# 3.net
KiCad netlist of a schematic drawn in Altium Designer
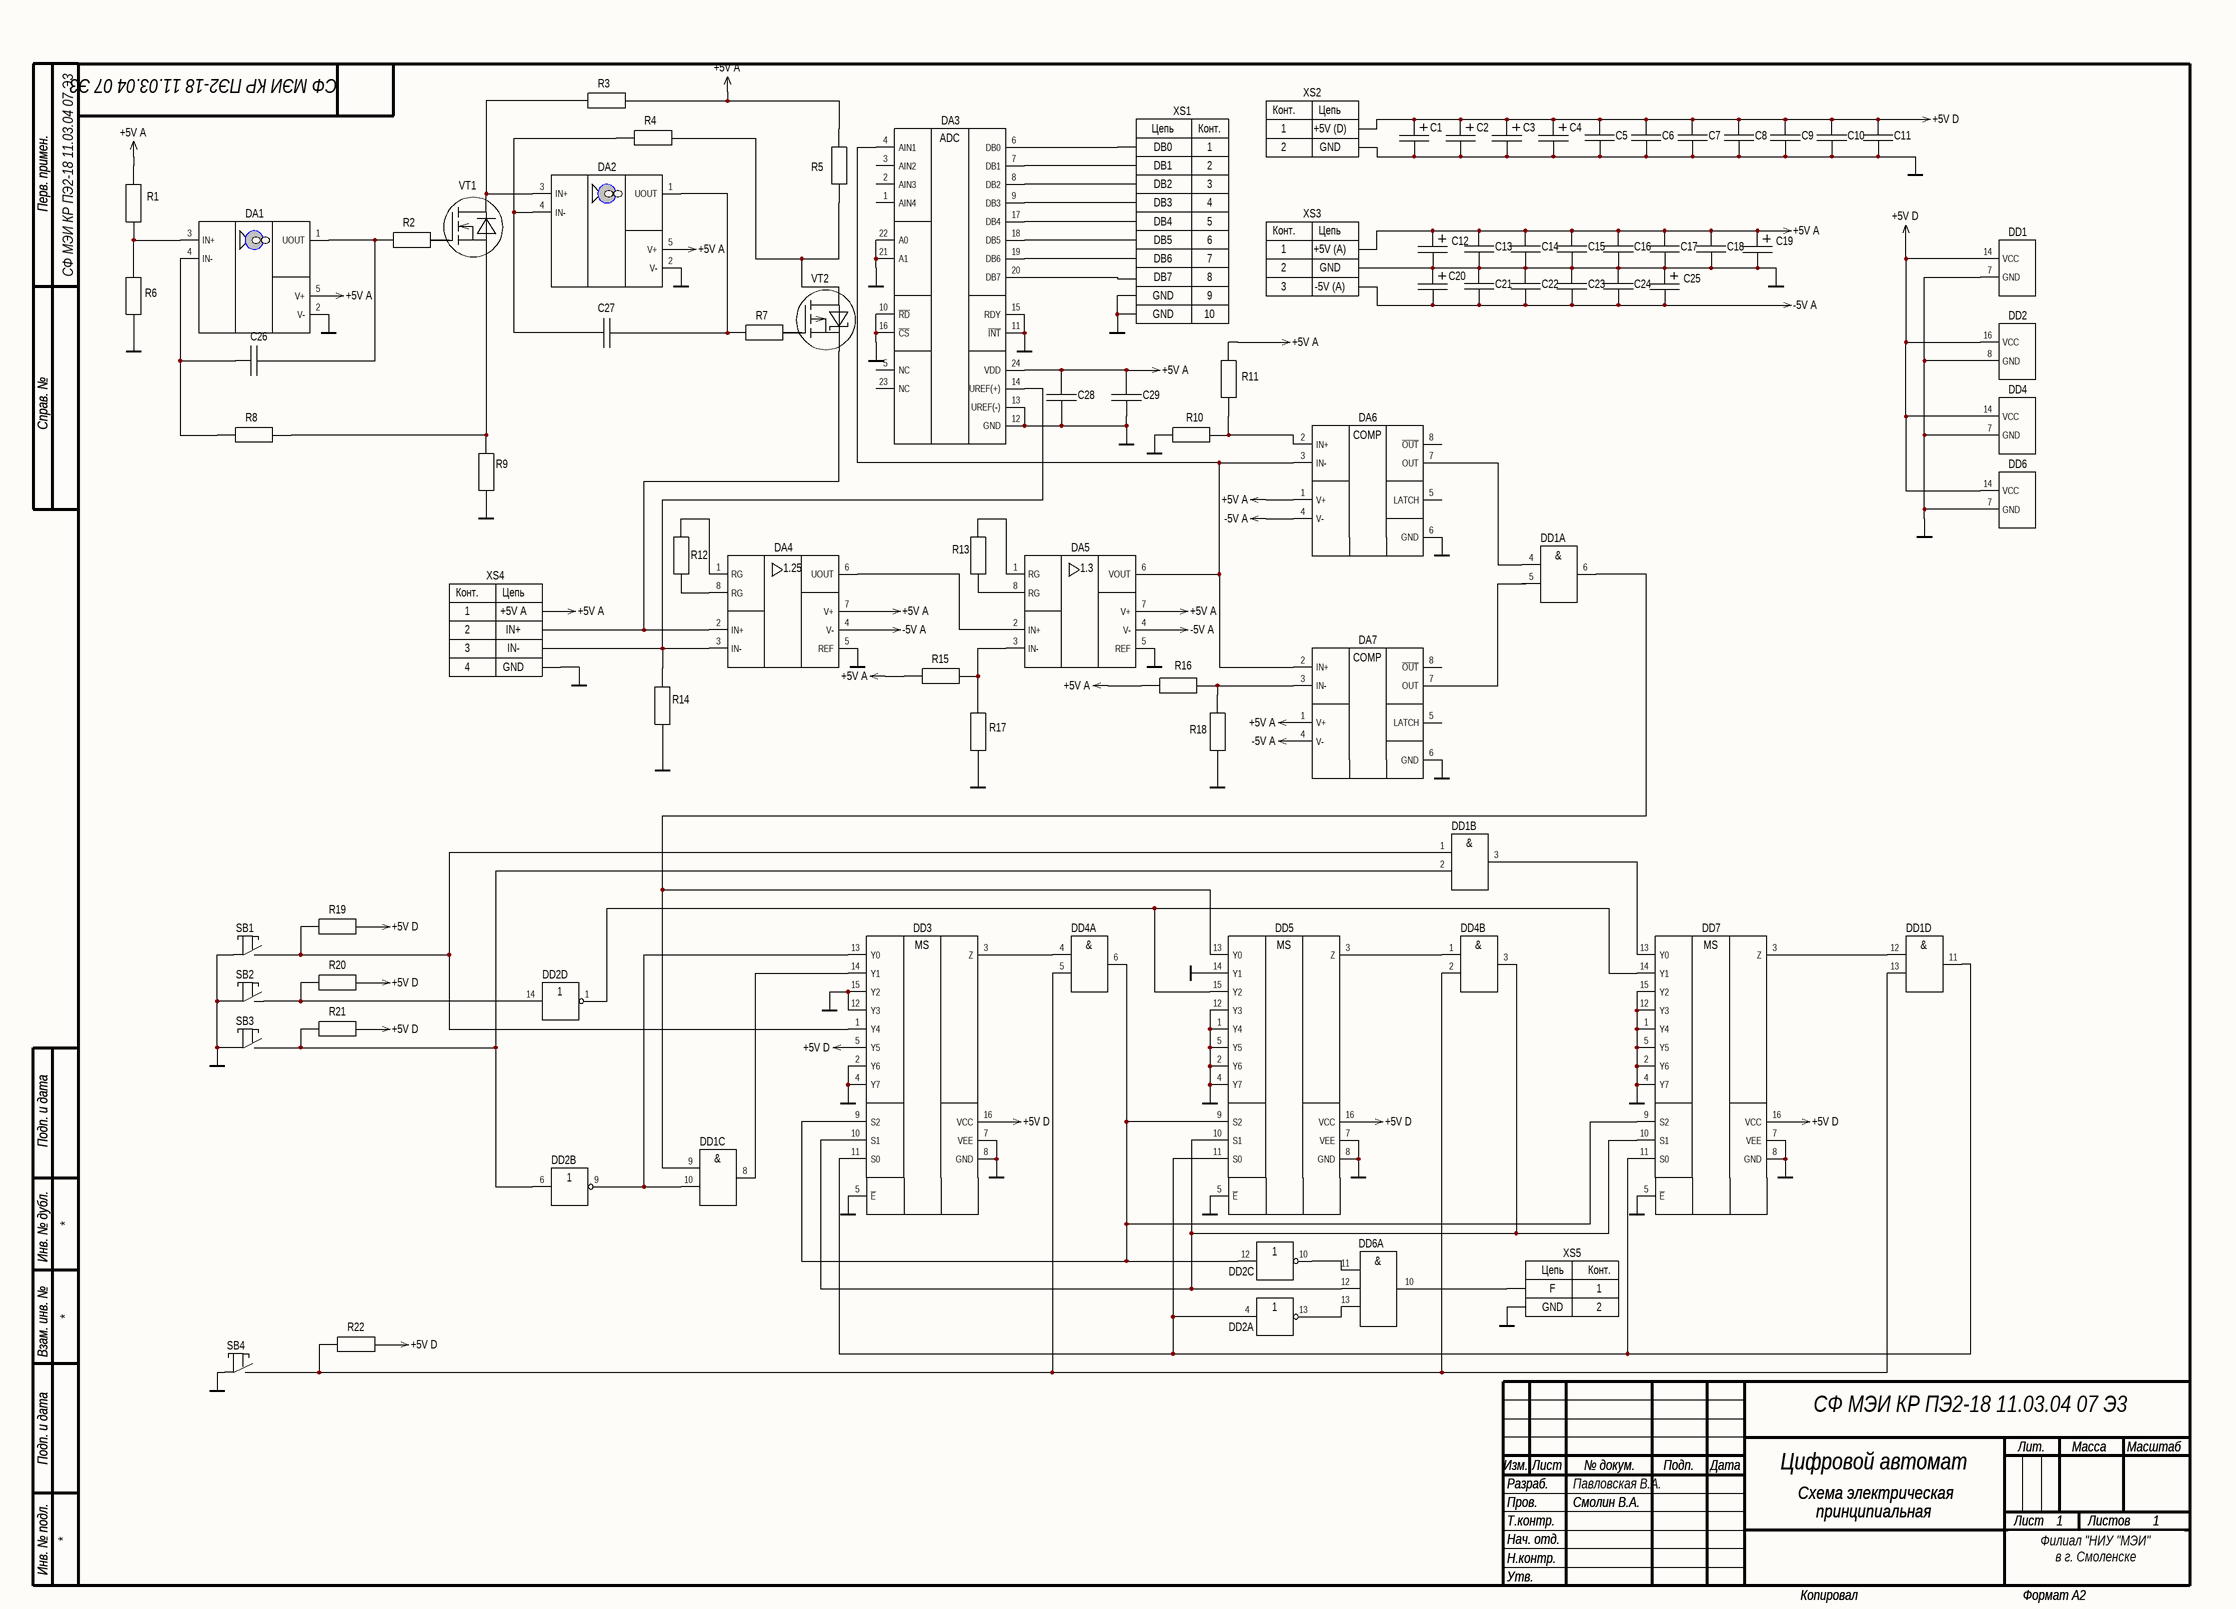
[diagram p0: Схема принципиальная3.SchDoc]

(export (version "E")
  (design (tool "Eeschema 10.0.6"))
  (components
    (comp (ref "C5")
      (value "0.1uF")
      (footprint "Кер.ЧИП конд. 0.1 мкФ X7R 50В 10% 0805")
      (description "Кер.ЧИП конд. 0.1 мкФ X7R 50В 10% 0805")
      (libsource (lib "УГО") (part "Кер.ЧИП конд. 0.1 мкФ X7R 50В 10% 0805"))
    )
    (comp (ref "C6")
      (value "0.1uF")
      (footprint "Кер.ЧИП конд. 0.1 мкФ X7R 50В 10% 0805")
      (description "Кер.ЧИП конд. 0.1 мкФ X7R 50В 10% 0805")
      (libsource (lib "УГО") (part "Кер.ЧИП конд. 0.1 мкФ X7R 50В 10% 0805"))
    )
    (comp (ref "C7")
      (value "0.1uF")
      (footprint "Кер.ЧИП конд. 0.1 мкФ X7R 50В 10% 0805")
      (description "Кер.ЧИП конд. 0.1 мкФ X7R 50В 10% 0805")
      (libsource (lib "УГО") (part "Кер.ЧИП конд. 0.1 мкФ X7R 50В 10% 0805"))
    )
    (comp (ref "C8")
      (value "0.1uF")
      (footprint "Кер.ЧИП конд. 0.1 мкФ X7R 50В 10% 0805")
      (description "Кер.ЧИП конд. 0.1 мкФ X7R 50В 10% 0805")
      (libsource (lib "УГО") (part "Кер.ЧИП конд. 0.1 мкФ X7R 50В 10% 0805"))
    )
    (comp (ref "C9")
      (value "0.1uF")
      (footprint "Кер.ЧИП конд. 0.1 мкФ X7R 50В 10% 0805")
      (description "Кер.ЧИП конд. 0.1 мкФ X7R 50В 10% 0805")
      (libsource (lib "УГО") (part "Кер.ЧИП конд. 0.1 мкФ X7R 50В 10% 0805"))
    )
    (comp (ref "C10")
      (value "0.1uF")
      (footprint "Кер.ЧИП конд. 0.1 мкФ X7R 50В 10% 0805")
      (description "Кер.ЧИП конд. 0.1 мкФ X7R 50В 10% 0805")
      (libsource (lib "УГО") (part "Кер.ЧИП конд. 0.1 мкФ X7R 50В 10% 0805"))
    )
    (comp (ref "C11")
      (value "0.1uF")
      (footprint "Кер.ЧИП конд. 0.1 мкФ X7R 50В 10% 0805")
      (description "Кер.ЧИП конд. 0.1 мкФ X7R 50В 10% 0805")
      (libsource (lib "УГО") (part "Кер.ЧИП конд. 0.1 мкФ X7R 50В 10% 0805"))
    )
    (comp (ref "C13")
      (value "0.1uF")
      (footprint "Кер.ЧИП конд. 0.1 мкФ X7R 50В 10% 0805")
      (description "Кер.ЧИП конд. 0.1 мкФ X7R 50В 10% 0805")
      (libsource (lib "УГО") (part "Кер.ЧИП конд. 0.1 мкФ X7R 50В 10% 0805"))
    )
    (comp (ref "C14")
      (value "0.1uF")
      (footprint "Кер.ЧИП конд. 0.1 мкФ X7R 50В 10% 0805")
      (description "Кер.ЧИП конд. 0.1 мкФ X7R 50В 10% 0805")
      (libsource (lib "УГО") (part "Кер.ЧИП конд. 0.1 мкФ X7R 50В 10% 0805"))
    )
    (comp (ref "C15")
      (value "0.1uF")
      (footprint "Кер.ЧИП конд. 0.1 мкФ X7R 50В 10% 0805")
      (description "Кер.ЧИП конд. 0.1 мкФ X7R 50В 10% 0805")
      (libsource (lib "УГО") (part "Кер.ЧИП конд. 0.1 мкФ X7R 50В 10% 0805"))
    )
    (comp (ref "C16")
      (value "0.1uF")
      (footprint "Кер.ЧИП конд. 0.1 мкФ X7R 50В 10% 0805")
      (description "Кер.ЧИП конд. 0.1 мкФ X7R 50В 10% 0805")
      (libsource (lib "УГО") (part "Кер.ЧИП конд. 0.1 мкФ X7R 50В 10% 0805"))
    )
    (comp (ref "C17")
      (value "0.1uF")
      (footprint "Кер.ЧИП конд. 0.1 мкФ X7R 50В 10% 0805")
      (description "Кер.ЧИП конд. 0.1 мкФ X7R 50В 10% 0805")
      (libsource (lib "УГО") (part "Кер.ЧИП конд. 0.1 мкФ X7R 50В 10% 0805"))
    )
    (comp (ref "C18")
      (value "0.1uF")
      (footprint "Кер.ЧИП конд. 0.1 мкФ X7R 50В 10% 0805")
      (description "Кер.ЧИП конд. 0.1 мкФ X7R 50В 10% 0805")
      (libsource (lib "УГО") (part "Кер.ЧИП конд. 0.1 мкФ X7R 50В 10% 0805"))
    )
    (comp (ref "C21")
      (value "0.1uF")
      (footprint "Кер.ЧИП конд. 0.1 мкФ X7R 50В 10% 0805")
      (description "Кер.ЧИП конд. 0.1 мкФ X7R 50В 10% 0805")
      (libsource (lib "УГО") (part "Кер.ЧИП конд. 0.1 мкФ X7R 50В 10% 0805"))
    )
    (comp (ref "C22")
      (value "0.1uF")
      (footprint "Кер.ЧИП конд. 0.1 мкФ X7R 50В 10% 0805")
      (description "Кер.ЧИП конд. 0.1 мкФ X7R 50В 10% 0805")
      (libsource (lib "УГО") (part "Кер.ЧИП конд. 0.1 мкФ X7R 50В 10% 0805"))
    )
    (comp (ref "C23")
      (value "0.1uF")
      (footprint "Кер.ЧИП конд. 0.1 мкФ X7R 50В 10% 0805")
      (description "Кер.ЧИП конд. 0.1 мкФ X7R 50В 10% 0805")
      (libsource (lib "УГО") (part "Кер.ЧИП конд. 0.1 мкФ X7R 50В 10% 0805"))
    )
    (comp (ref "C24")
      (value "0.1uF")
      (footprint "Кер.ЧИП конд. 0.1 мкФ X7R 50В 10% 0805")
      (description "Кер.ЧИП конд. 0.1 мкФ X7R 50В 10% 0805")
      (libsource (lib "УГО") (part "Кер.ЧИП конд. 0.1 мкФ X7R 50В 10% 0805"))
    )
    (comp (ref "C26")
      (value "1000pF")
      (footprint "Кер.ЧИП конд. 100пФ NPO 50В 5% 0805, GRM2165C1H101J")
      (description "Кер.ЧИП конд. 100пФ NPO 50В 5% 0805, GRM2165C1H101J")
      (libsource (lib "УГО") (part "Кер.ЧИП конд. 100пФ NPO 50В 5% 0805, GRM2165C1H101J"))
    )
    (comp (ref "C27")
      (value "2200pF")
      (footprint "Кер.ЧИП конд. 100пФ NPO 50В 5% 0805, GRM2165C1H101J")
      (description "Кер.ЧИП конд. 100пФ NPO 50В 5% 0805, GRM2165C1H101J")
      (libsource (lib "УГО") (part "Кер.ЧИП конд. 100пФ NPO 50В 5% 0805, GRM2165C1H101J"))
    )
    (comp (ref "C28")
      (value "0.1uF")
      (footprint "Кер.ЧИП конд. 0.1 мкФ X7R 50В 10% 0805")
      (description "Кер.ЧИП конд. 0.1 мкФ X7R 50В 10% 0805")
      (libsource (lib "УГО") (part "Кер.ЧИП конд. 0.1 мкФ X7R 50В 10% 0805"))
    )
    (comp (ref "C29")
      (value "47uF")
      (footprint "Кер.ЧИП конд. 47 мкФ X5R 20% 10В 1206")
      (description "Кер.ЧИП конд. 47 мкФ X5R 20% 10В 1206")
      (libsource (lib "УГО") (part "Кер.ЧИП конд. 47 мкФ X5R 20% 10В 1206"))
    )
    (comp (ref "DA1")
      (value "DA6")
      (footprint "ОУ для источника тока")
      (description "ОУ")
      (libsource (lib "УГО") (part "OPAx333 1.8-V, microPower, CMOS Operational Amplifiers, Zero-Drift Series"))
    )
    (comp (ref "DA2")
      (value "DA7")
      (footprint "ОУ для источника тока")
      (description "ОУ")
      (libsource (lib "УГО") (part "OPAx333 1.8-V, microPower, CMOS Operational Amplifiers, Zero-Drift Series"))
    )
    (comp (ref "DA4")
      (value "INA118E_BB")
      (footprint "AD620 Инструмент.усилитель")
      (libsource (lib "УГО") (part "INA118E_BB"))
    )
    (comp (ref "DA5")
      (value "INA118E_BB_1")
      (footprint "AD620 Инструмент.усилитель")
      (libsource (lib "УГО") (part "INA118E_BB_1"))
    )
    (comp (ref "DA6") (value "AD8561") (footprint "AD8561") (libsource (lib "УГО") (part "AD8561")))
    (comp (ref "DA7") (value "AD8561") (footprint "AD8561") (libsource (lib "УГО") (part "AD8561")))
    (comp (ref "DA33") (value "AD7824") (footprint "AD7824") (libsource (lib "УГО") (part "AD7824")))
    (comp (ref "DD1")
      (value "И №1 (4 компонента)")
      (footprint "4x2И")
      (libsource (lib "УГО") (part "И №1 (4 компонента)"))
    )
    (comp (ref "DD2")
      (value "НЕ №3 (4 компонента)")
      (footprint "CD4044B")
      (libsource (lib "УГО") (part "НЕ №3 (4 компонента)"))
    )
    (comp (ref "DD3")
      (value "74HC40510")
      (footprint "Мультиплексор")
      (libsource (lib "УГО") (part "Мультиплексор"))
    )
    (comp (ref "DD4")
      (value "И №2 (2 компонента)")
      (footprint "4x2И")
      (libsource (lib "УГО") (part "И №2 (2 компонента)"))
    )
    (comp (ref "DD5")
      (value "74HC40510")
      (footprint "Мультиплексор")
      (libsource (lib "УГО") (part "Мультиплексор"))
    )
    (comp (ref "DD6") (value "3И №1") (footprint "4x2И") (libsource (lib "УГО") (part "3И №1")))
    (comp (ref "DD7")
      (value "74HC40510")
      (footprint "Мультиплексор")
      (libsource (lib "УГО") (part "Мультиплексор"))
    )
    (comp (ref "R1")
      (value "3k")
      (footprint "0.125Вт 0805 3 кОм, 5%, Чип резистор (SMD)")
      (description "0.125Вт 0805 5кОм, 5%, Чип резистор (SMD)")
      (libsource (lib "УГО") (part "0.125Вт 0805 5кОм, 5%, Чип резистор (SMD)"))
    )
    (comp (ref "R2")
      (value "200")
      (footprint "0.125Вт 0805 3 кОм, 5%, Чип резистор (SMD)")
      (description "0.125Вт 0805 5кОм, 5%, Чип резистор (SMD)")
      (libsource (lib "УГО") (part "0.125Вт 0805 5кОм, 5%, Чип резистор (SMD)"))
    )
    (comp (ref "R3")
      (value "470")
      (footprint "0.125Вт 0805 3 кОм, 5%, Чип резистор (SMD)")
      (description "0.125Вт 0805 5кОм, 5%, Чип резистор (SMD)")
      (libsource (lib "УГО") (part "0.125Вт 0805 5кОм, 5%, Чип резистор (SMD)"))
    )
    (comp (ref "R4")
      (value "10k")
      (footprint "0.125Вт 0805 3 кОм, 5%, Чип резистор (SMD)")
      (description "0.125Вт 0805 5кОм, 5%, Чип резистор (SMD)")
      (libsource (lib "УГО") (part "0.125Вт 0805 5кОм, 5%, Чип резистор (SMD)"))
    )
    (comp (ref "R5")
      (value "4.7")
      (footprint "0.125Вт 0805 3 кОм, 5%, Чип резистор (SMD)")
      (description "0.125Вт 0805 5кОм, 5%, Чип резистор (SMD)")
      (libsource (lib "УГО") (part "0.125Вт 0805 5кОм, 5%, Чип резистор (SMD)"))
    )
    (comp (ref "R6")
      (value "2k")
      (footprint "0.125Вт 0805 3 кОм, 5%, Чип резистор (SMD)")
      (description "0.125Вт 0805 5кОм, 5%, Чип резистор (SMD)")
      (libsource (lib "УГО") (part "0.125Вт 0805 5кОм, 5%, Чип резистор (SMD)"))
    )
    (comp (ref "R7")
      (value "330")
      (footprint "0.125Вт 0805 3 кОм, 5%, Чип резистор (SMD)")
      (description "0.125Вт 0805 5кОм, 5%, Чип резистор (SMD)")
      (libsource (lib "УГО") (part "0.125Вт 0805 5кОм, 5%, Чип резистор (SMD)"))
    )
    (comp (ref "R8")
      (value "10k")
      (footprint "0.125Вт 0805 3 кОм, 5%, Чип резистор (SMD)")
      (description "0.125Вт 0805 5кОм, 5%, Чип резистор (SMD)")
      (libsource (lib "УГО") (part "0.125Вт 0805 5кОм, 5%, Чип резистор (SMD)"))
    )
    (comp (ref "R9")
      (value "2k")
      (footprint "0.125Вт 0805 3 кОм, 5%, Чип резистор (SMD)")
      (description "0.125Вт 0805 5кОм, 5%, Чип резистор (SMD)")
      (libsource (lib "УГО") (part "0.125Вт 0805 5кОм, 5%, Чип резистор (SMD)"))
    )
    (comp (ref "R10")
      (value "1.5k")
      (footprint "0.125Вт 0805 15Ом, 5%, Чип резистор (SMD)")
      (description "0.125Вт 0805 15Ом, 5%, Чип резистор (SMD)")
      (libsource (lib "УГО") (part "0.125Вт 0805 15Ом, 5%, Чип резистор (SMD)_2_1"))
    )
    (comp (ref "R11")
      (value "8.2k")
      (footprint "0.125Вт 0805 82Ом, 5%, Чип резистор (SMD)")
      (description "0.125Вт 0805 82Ом, 5%, Чип резистор (SMD)")
      (libsource (lib "УГО") (part "0.125Вт 0805 82Ом, 5%, Чип резистор (SMD)_2_2"))
    )
    (comp (ref "R12")
      (value "200k")
      (footprint "0.125Вт 0805 200 кОм, 5%, Чип резистор (SMD)")
      (description "0.125Вт 0805 200 кОм, 5%, Чип резистор (SMD)")
      (libsource (lib "УГО") (part "0.125Вт 0805 200 кОм, 5%, Чип резистор (SMD)"))
    )
    (comp (ref "R13")
      (value "160k")
      (footprint "0.125Вт 0805 160 кОм, 5%, Чип резистор (SMD)")
      (description "0.125Вт 0805 160 кОм, 5%, Чип резистор (SMD)")
      (libsource (lib "УГО") (part "0.125Вт 0805 160 кОм, 5%, Чип резистор (SMD)"))
    )
    (comp (ref "R14")
      (value "51k")
      (footprint "0.125Вт 0805 51 кОм, 5%, Чип резистор (SMD)")
      (description "0.125Вт 0805 51 кОм, 5%, Чип резистор (SMD)")
      (libsource (lib "УГО") (part "0.125Вт 0805 51 кОм, 5%, Чип резистор (SMD)"))
    )
    (comp (ref "R15")
      (value "7.5k")
      (footprint "0.125Вт 0805 75Ом, 5%, Чип резистор (SMD)")
      (description "0.125Вт 0805 75Ом, 5%, Чип резистор (SMD)")
      (libsource (lib "УГО") (part "0.125Вт 0805 75Ом, 5%, Чип резистор (SMD)"))
    )
    (comp (ref "R16")
      (value "1k")
      (footprint "0.125Вт 0805 91Ом, 5%, Чип резистор (SMD)")
      (description "0.125Вт 0805 91Ом, 5%, Чип резистор (SMD)")
      (libsource (lib "УГО") (part "0.125Вт 0805 91кОм, 5%, Чип резистор (SMD)_1"))
    )
    (comp (ref "R17")
      (value "2.2k")
      (footprint "0.125Вт 0805 22Ом, 5%, Чип резистор (SMD)")
      (description "0.125Вт 0805 22Ом, 5%, Чип резистор (SMD)")
      (libsource (lib "УГО") (part "0.125Вт 0805 22Ом, 5%, Чип резистор (SMD)"))
    )
    (comp (ref "R18")
      (value "56")
      (footprint "0.125Вт 0805 5.1Ом, 5%, Чип резистор (SMD)")
      (description "0.125Вт 0805 5.1Ом, 5%, Чип резистор (SMD)")
      (libsource (lib "УГО") (part "0.125Вт 0805 5.1Ом, 5%, Чип резистор (SMD)_2"))
    )
    (comp (ref "R19")
      (value "10k")
      (footprint "0.125Вт 0805 3 кОм, 5%, Чип резистор (SMD)")
      (description "0.125Вт 0805 5кОм, 5%, Чип резистор (SMD)")
      (libsource (lib "УГО") (part "0.125Вт 0805 5кОм, 5%, Чип резистор (SMD)"))
    )
    (comp (ref "R20")
      (value "10k")
      (footprint "0.125Вт 0805 3 кОм, 5%, Чип резистор (SMD)")
      (description "0.125Вт 0805 5кОм, 5%, Чип резистор (SMD)")
      (libsource (lib "УГО") (part "0.125Вт 0805 5кОм, 5%, Чип резистор (SMD)"))
    )
    (comp (ref "R21")
      (value "10k")
      (footprint "0.125Вт 0805 3 кОм, 5%, Чип резистор (SMD)")
      (description "0.125Вт 0805 5кОм, 5%, Чип резистор (SMD)")
      (libsource (lib "УГО") (part "0.125Вт 0805 5кОм, 5%, Чип резистор (SMD)"))
    )
    (comp (ref "R22")
      (value "10k")
      (footprint "0.125Вт 0805 3 кОм, 5%, Чип резистор (SMD)")
      (description "0.125Вт 0805 5кОм, 5%, Чип резистор (SMD)")
      (libsource (lib "УГО") (part "0.125Вт 0805 5кОм, 5%, Чип резистор (SMD)"))
    )
    (comp (ref "SB1")
      (value "Выключатель кнопочный с замыкающим контактом")
      (footprint "Выключатель кнопочный ese21x")
      (libsource (lib "УГО") (part "Выключатель кнопочный с замыкающим контактом"))
    )
    (comp (ref "SB2")
      (value "Выключатель кнопочный с замыкающим контактом")
      (footprint "Выключатель кнопочный ese21x")
      (libsource (lib "УГО") (part "Выключатель кнопочный с замыкающим контактом"))
    )
    (comp (ref "SB3")
      (value "Выключатель кнопочный с замыкающим контактом")
      (footprint "Выключатель кнопочный ese21x")
      (libsource (lib "УГО") (part "Выключатель кнопочный с замыкающим контактом"))
    )
    (comp (ref "SB4")
      (value "Выключатель кнопочный с замыкающим контактом")
      (footprint "Выключатель кнопочный ese21x")
      (libsource (lib "УГО") (part "Выключатель кнопочный с замыкающим контактом"))
    )
    (comp (ref "VT1")
      (value "Транзистор N-канальный")
      (footprint "Транзистор N-канальный")
      (description "SI2304DDS-T1-GE3")
      (libsource (lib "УГО") (part "Транзистор N-канальный"))
    )
    (comp (ref "VT2")
      (value "Транзистор р-канальный")
      (footprint "Транзистор р-канальный")
      (description "NTF2955T1G, МОП-транзистор, P Канал, 2.6 А, -60 В, 0.17 Ом, 20 В, -4 В")
      (libsource (lib "УГО") (part "Транзистор р-канальный"))
    )
    (comp (ref "XS1") (value "XS 10Pin") (footprint "CI1108M1H") (libsource (lib "УГО") (part "XS 10Pin")))
    (comp (ref "XS2")
      (value "XS 2Pin (D)")
      (footprint "CI1102M1H  (F)")
      (libsource (lib "УГО") (part "XS 2Pin (D)"))
    )
    (comp (ref "XS3")
      (value "XS 3Pin (A)")
      (footprint "CI1108M1H - duplicate")
      (libsource (lib "УГО") (part "XS 3Pin (A)"))
    )
    (comp (ref "XS4") (value "XS Датчик") (footprint "CI1102M1H") (libsource (lib "УГО") (part "XS Датчик")))
    (comp (ref "XS5")
      (value "XS 2Pin_1")
      (footprint "CI1102M1H  (F)")
      (libsource (lib "УГО") (part "XS 2Pin_1"))
    )
    (comp (ref "С1")
      (value "1uF")
      (footprint "ECAP SMD, 1 мкФ, 50В, Конденсатор электролитический алюминиевый SMD")
      (description "ECAP SMD, 1 мкФ, 50В, Конденсатор электролитический алюминиевый SMD")
      (libsource (lib "УГО") (part "ECAP SMD, 1 мкФ, 50В, Конденсатор электролитический алюминиевый SMD"))
    )
    (comp (ref "С2")
      (value "1uF")
      (footprint "ECAP SMD, 1 мкФ, 50В, Конденсатор электролитический алюминиевый SMD")
      (description "ECAP SMD, 1 мкФ, 50В, Конденсатор электролитический алюминиевый SMD")
      (libsource (lib "УГО") (part "ECAP SMD, 1 мкФ, 50В, Конденсатор электролитический алюминиевый SMD"))
    )
    (comp (ref "С3")
      (value "1uF")
      (footprint "ECAP SMD, 1 мкФ, 50В, Конденсатор электролитический алюминиевый SMD")
      (description "ECAP SMD, 1 мкФ, 50В, Конденсатор электролитический алюминиевый SMD")
      (libsource (lib "УГО") (part "ECAP SMD, 1 мкФ, 50В, Конденсатор электролитический алюминиевый SMD"))
    )
    (comp (ref "С4")
      (value "1uF")
      (footprint "ECAP SMD, 1 мкФ, 50В, Конденсатор электролитический алюминиевый SMD")
      (description "ECAP SMD, 1 мкФ, 50В, Конденсатор электролитический алюминиевый SMD")
      (libsource (lib "УГО") (part "ECAP SMD, 1 мкФ, 50В, Конденсатор электролитический алюминиевый SMD"))
    )
    (comp (ref "С12")
      (value "1uF")
      (footprint "ECAP SMD, 1 мкФ, 50В, Конденсатор электролитический алюминиевый SMD")
      (description "ECAP SMD, 1 мкФ, 50В, Конденсатор электролитический алюминиевый SMD")
      (libsource (lib "УГО") (part "ECAP SMD, 1 мкФ, 50В, Конденсатор электролитический алюминиевый SMD"))
    )
    (comp (ref "С19")
      (value "1uF")
      (footprint "ECAP SMD, 1 мкФ, 50В, Конденсатор электролитический алюминиевый SMD")
      (description "ECAP SMD, 1 мкФ, 50В, Конденсатор электролитический алюминиевый SMD")
      (libsource (lib "УГО") (part "ECAP SMD, 1 мкФ, 50В, Конденсатор электролитический алюминиевый SMD"))
    )
    (comp (ref "С20")
      (value "1uF")
      (footprint "ECAP SMD, 1 мкФ, 50В, Конденсатор электролитический алюминиевый SMD")
      (description "ECAP SMD, 1 мкФ, 50В, Конденсатор электролитический алюминиевый SMD")
      (libsource (lib "УГО") (part "ECAP SMD, 1 мкФ, 50В, Конденсатор электролитический алюминиевый SMD"))
    )
    (comp (ref "С25")
      (value "1uF")
      (footprint "ECAP SMD, 1 мкФ, 50В, Конденсатор электролитический алюминиевый SMD")
      (description "ECAP SMD, 1 мкФ, 50В, Конденсатор электролитический алюминиевый SMD")
      (libsource (lib "УГО") (part "ECAP SMD, 1 мкФ, 50В, Конденсатор электролитический алюминиевый SMD"))
    )
  )
  (nets
    (net (code "1") (name "+5V A") (class "Default")
      (node (ref "C13") (pin "2") (pinfunction "2_2") (pintype "passive"))
      (node (ref "C14") (pin "2") (pinfunction "2_2") (pintype "passive"))
      (node (ref "C15") (pin "2") (pinfunction "2_2") (pintype "passive"))
      (node (ref "C16") (pin "2") (pinfunction "2_2") (pintype "passive"))
      (node (ref "C17") (pin "2") (pinfunction "2_2") (pintype "passive"))
      (node (ref "C18") (pin "2") (pinfunction "2_2") (pintype "passive"))
      (node (ref "C28") (pin "2") (pinfunction "2_2") (pintype "passive"))
      (node (ref "C29") (pin "2") (pinfunction "2_2") (pintype "passive"))
      (node (ref "DA1") (pin "5") (pinfunction "V+_5") (pintype "passive"))
      (node (ref "DA2") (pin "5") (pinfunction "V+_5") (pintype "passive"))
      (node (ref "DA33") (pin "24") (pinfunction "VDD_24") (pintype "passive"))
      (node (ref "DA4") (pin "7") (pinfunction "V+_7") (pintype "passive"))
      (node (ref "DA5") (pin "7") (pinfunction "V+_7") (pintype "passive"))
      (node (ref "DA6") (pin "1") (pinfunction "V+_1") (pintype "passive"))
      (node (ref "DA7") (pin "1") (pinfunction "V+_1") (pintype "passive"))
      (node (ref "R1") (pin "1") (pinfunction "1_1") (pintype "passive"))
      (node (ref "R11") (pin "2") (pinfunction "2_2") (pintype "passive"))
      (node (ref "R15") (pin "1") (pinfunction "1_1") (pintype "passive"))
      (node (ref "R16") (pin "1") (pinfunction "1_1") (pintype "passive"))
      (node (ref "R3") (pin "2") (pinfunction "2_2") (pintype "passive"))
      (node (ref "R5") (pin "2") (pinfunction "2_2") (pintype "passive"))
      (node (ref "XS3") (pin "1") (pinfunction "Pin1_1") (pintype "passive"))
      (node (ref "XS4") (pin "1") (pinfunction "Pin1_1") (pintype "passive"))
      (node (ref "С12") (pin "1") (pinfunction "1_1") (pintype "passive"))
      (node (ref "С19") (pin "1") (pinfunction "1_1") (pintype "passive"))
    )
    (net (code "2") (name "+5V D") (class "Default")
      (node (ref "C10") (pin "2") (pinfunction "2_2") (pintype "passive"))
      (node (ref "C11") (pin "2") (pinfunction "2_2") (pintype "passive"))
      (node (ref "C5") (pin "2") (pinfunction "2_2") (pintype "passive"))
      (node (ref "C6") (pin "2") (pinfunction "2_2") (pintype "passive"))
      (node (ref "C7") (pin "2") (pinfunction "2_2") (pintype "passive"))
      (node (ref "C8") (pin "2") (pinfunction "2_2") (pintype "passive"))
      (node (ref "C9") (pin "2") (pinfunction "2_2") (pintype "passive"))
      (node (ref "DD1") (pin "14") (pinfunction "VCC_14") (pintype "passive"))
      (node (ref "DD2") (pin "16") (pinfunction "VCC_16") (pintype "passive"))
      (node (ref "DD3") (pin "16") (pinfunction "VCC_16") (pintype "passive"))
      (node (ref "DD3") (pin "5") (pinfunction "Y5_5") (pintype "passive"))
      (node (ref "DD4") (pin "14") (pinfunction "VCC_14") (pintype "passive"))
      (node (ref "DD5") (pin "16") (pinfunction "VCC_16") (pintype "passive"))
      (node (ref "DD6") (pin "14") (pinfunction "VCC_14") (pintype "passive"))
      (node (ref "DD7") (pin "16") (pinfunction "VCC_16") (pintype "passive"))
      (node (ref "R19") (pin "2") (pinfunction "2_2") (pintype "passive"))
      (node (ref "R20") (pin "2") (pinfunction "2_2") (pintype "passive"))
      (node (ref "R21") (pin "2") (pinfunction "2_2") (pintype "passive"))
      (node (ref "R22") (pin "2") (pinfunction "2_2") (pintype "passive"))
      (node (ref "XS2") (pin "1") (pinfunction "Pin1_1") (pintype "passive"))
      (node (ref "С1") (pin "1") (pinfunction "1_1") (pintype "passive"))
      (node (ref "С2") (pin "1") (pinfunction "1_1") (pintype "passive"))
      (node (ref "С3") (pin "1") (pinfunction "1_1") (pintype "passive"))
      (node (ref "С4") (pin "1") (pinfunction "1_1") (pintype "passive"))
    )
    (net (code "3") (name "-5V A") (class "Default")
      (node (ref "C21") (pin "1") (pinfunction "1_1") (pintype "passive"))
      (node (ref "C22") (pin "1") (pinfunction "1_1") (pintype "passive"))
      (node (ref "C23") (pin "1") (pinfunction "1_1") (pintype "passive"))
      (node (ref "C24") (pin "1") (pinfunction "1_1") (pintype "passive"))
      (node (ref "DA4") (pin "4") (pinfunction "V-_4") (pintype "passive"))
      (node (ref "DA5") (pin "4") (pinfunction "V-_4") (pintype "passive"))
      (node (ref "DA6") (pin "4") (pinfunction "V-_4") (pintype "passive"))
      (node (ref "DA7") (pin "4") (pinfunction "V-_4") (pintype "passive"))
      (node (ref "XS3") (pin "3") (pinfunction "Pin3_3") (pintype "passive"))
      (node (ref "С20") (pin "2") (pinfunction "2_2") (pintype "passive"))
      (node (ref "С25") (pin "2") (pinfunction "2_2") (pintype "passive"))
    )
    (net (code "4") (name "GND A") (class "Default")
      (node (ref "C13") (pin "1") (pinfunction "1_1") (pintype "passive"))
      (node (ref "C14") (pin "1") (pinfunction "1_1") (pintype "passive"))
      (node (ref "C15") (pin "1") (pinfunction "1_1") (pintype "passive"))
      (node (ref "C16") (pin "1") (pinfunction "1_1") (pintype "passive"))
      (node (ref "C17") (pin "1") (pinfunction "1_1") (pintype "passive"))
      (node (ref "C18") (pin "1") (pinfunction "1_1") (pintype "passive"))
      (node (ref "C21") (pin "2") (pinfunction "2_2") (pintype "passive"))
      (node (ref "C22") (pin "2") (pinfunction "2_2") (pintype "passive"))
      (node (ref "C23") (pin "2") (pinfunction "2_2") (pintype "passive"))
      (node (ref "C24") (pin "2") (pinfunction "2_2") (pintype "passive"))
      (node (ref "C28") (pin "1") (pinfunction "1_1") (pintype "passive"))
      (node (ref "C29") (pin "1") (pinfunction "1_1") (pintype "passive"))
      (node (ref "DA1") (pin "2") (pinfunction "V-_2") (pintype "passive"))
      (node (ref "DA2") (pin "2") (pinfunction "V-_2") (pintype "passive"))
      (node (ref "DA33") (pin "10") (pinfunction "~{RD}_10") (pintype "passive"))
      (node (ref "DA33") (pin "11") (pinfunction "~{INT}_11") (pintype "passive"))
      (node (ref "DA33") (pin "12") (pinfunction "GND_12") (pintype "passive"))
      (node (ref "DA33") (pin "13") (pinfunction "UREF(-)_13") (pintype "passive"))
      (node (ref "DA33") (pin "15") (pinfunction "RDY_15") (pintype "passive"))
      (node (ref "DA33") (pin "16") (pinfunction "~{CS}_16") (pintype "passive"))
      (node (ref "DA33") (pin "21") (pinfunction "A1_21") (pintype "passive"))
      (node (ref "DA33") (pin "22") (pinfunction "A0_22") (pintype "passive"))
      (node (ref "DA4") (pin "5") (pinfunction "REF_5") (pintype "passive"))
      (node (ref "DA5") (pin "5") (pinfunction "REF_5") (pintype "passive"))
      (node (ref "DA6") (pin "6") (pinfunction "GND_6") (pintype "passive"))
      (node (ref "DA7") (pin "6") (pinfunction "GND_6") (pintype "passive"))
      (node (ref "R10") (pin "1") (pinfunction "1_1") (pintype "passive"))
      (node (ref "R14") (pin "2") (pinfunction "2_2") (pintype "passive"))
      (node (ref "R17") (pin "1") (pinfunction "1_1") (pintype "passive"))
      (node (ref "R18") (pin "1") (pinfunction "1_1") (pintype "passive"))
      (node (ref "R6") (pin "2") (pinfunction "2_2") (pintype "passive"))
      (node (ref "R9") (pin "1") (pinfunction "1_1") (pintype "passive"))
      (node (ref "XS1") (pin "10") (pinfunction "Pin10_10") (pintype "passive"))
      (node (ref "XS1") (pin "9") (pinfunction "Pin9_9") (pintype "passive"))
      (node (ref "XS3") (pin "2") (pinfunction "Pin2_2") (pintype "passive"))
      (node (ref "XS4") (pin "4") (pinfunction "4_4") (pintype "passive"))
      (node (ref "С12") (pin "2") (pinfunction "2_2") (pintype "passive"))
      (node (ref "С19") (pin "2") (pinfunction "2_2") (pintype "passive"))
      (node (ref "С20") (pin "1") (pinfunction "1_1") (pintype "passive"))
      (node (ref "С25") (pin "1") (pinfunction "1_1") (pintype "passive"))
    )
    (net (code "5") (name "GND D") (class "Default")
      (node (ref "C10") (pin "1") (pinfunction "1_1") (pintype "passive"))
      (node (ref "C11") (pin "1") (pinfunction "1_1") (pintype "passive"))
      (node (ref "C5") (pin "1") (pinfunction "1_1") (pintype "passive"))
      (node (ref "C6") (pin "1") (pinfunction "1_1") (pintype "passive"))
      (node (ref "C7") (pin "1") (pinfunction "1_1") (pintype "passive"))
      (node (ref "C8") (pin "1") (pinfunction "1_1") (pintype "passive"))
      (node (ref "C9") (pin "1") (pinfunction "1_1") (pintype "passive"))
      (node (ref "DD1") (pin "7") (pinfunction "GND_7") (pintype "passive"))
      (node (ref "DD2") (pin "8") (pinfunction "GND_8") (pintype "passive"))
      (node (ref "DD3") (pin "12") (pinfunction "Y3_12") (pintype "passive"))
      (node (ref "DD3") (pin "15") (pinfunction "Y2_15") (pintype "passive"))
      (node (ref "DD3") (pin "2") (pinfunction "Y6_2") (pintype "passive"))
      (node (ref "DD3") (pin "4") (pinfunction "Y7_4") (pintype "passive"))
      (node (ref "DD3") (pin "5") (pinfunction "~{E}_5") (pintype "passive"))
      (node (ref "DD3") (pin "7") (pinfunction "VEE_7") (pintype "passive"))
      (node (ref "DD3") (pin "8") (pinfunction "GND_8") (pintype "passive"))
      (node (ref "DD4") (pin "7") (pinfunction "GND_7") (pintype "passive"))
      (node (ref "DD5") (pin "1") (pinfunction "Y4_1") (pintype "passive"))
      (node (ref "DD5") (pin "12") (pinfunction "Y3_12") (pintype "passive"))
      (node (ref "DD5") (pin "14") (pinfunction "Y1_14") (pintype "passive"))
      (node (ref "DD5") (pin "2") (pinfunction "Y6_2") (pintype "passive"))
      (node (ref "DD5") (pin "4") (pinfunction "Y7_4") (pintype "passive"))
      (node (ref "DD5") (pin "5") (pinfunction "Y5_5") (pintype "passive"))
      (node (ref "DD5") (pin "7") (pinfunction "VEE_7") (pintype "passive"))
      (node (ref "DD5") (pin "8") (pinfunction "GND_8") (pintype "passive"))
      (node (ref "DD6") (pin "7") (pinfunction "GND_7") (pintype "passive"))
      (node (ref "DD7") (pin "1") (pinfunction "Y4_1") (pintype "passive"))
      (node (ref "DD7") (pin "12") (pinfunction "Y3_12") (pintype "passive"))
      (node (ref "DD7") (pin "15") (pinfunction "Y2_15") (pintype "passive"))
      (node (ref "DD7") (pin "2") (pinfunction "Y6_2") (pintype "passive"))
      (node (ref "DD7") (pin "4") (pinfunction "Y7_4") (pintype "passive"))
      (node (ref "DD7") (pin "5") (pinfunction "Y5_5") (pintype "passive"))
      (node (ref "DD7") (pin "7") (pinfunction "VEE_7") (pintype "passive"))
      (node (ref "DD7") (pin "8") (pinfunction "GND_8") (pintype "passive"))
      (node (ref "SB1") (pin "1") (pintype "passive"))
      (node (ref "SB2") (pin "1") (pintype "passive"))
      (node (ref "SB3") (pin "1") (pintype "passive"))
      (node (ref "SB4") (pin "1") (pintype "passive"))
      (node (ref "XS2") (pin "2") (pinfunction "Pin2_2") (pintype "passive"))
      (node (ref "XS5") (pin "2") (pinfunction "Pin2_2") (pintype "passive"))
      (node (ref "С1") (pin "2") (pinfunction "2_2") (pintype "passive"))
      (node (ref "С2") (pin "2") (pinfunction "2_2") (pintype "passive"))
      (node (ref "С3") (pin "2") (pinfunction "2_2") (pintype "passive"))
      (node (ref "С4") (pin "2") (pinfunction "2_2") (pintype "passive"))
    )
    (net (code "6") (name "Net-(DA1-IN+)") (class "Default")
      (node (ref "DA1") (pin "3") (pinfunction "IN+_3") (pintype "passive"))
      (node (ref "R1") (pin "2") (pinfunction "2_2") (pintype "passive"))
      (node (ref "R6") (pin "1") (pinfunction "1_1") (pintype "passive"))
    )
    (net (code "7") (name "Net-(DA1-IN-)") (class "Default")
      (node (ref "C26") (pin "1") (pinfunction "1_1") (pintype "passive"))
      (node (ref "DA1") (pin "4") (pinfunction "IN-_4") (pintype "passive"))
      (node (ref "R8") (pin "1") (pinfunction "1_1") (pintype "passive"))
    )
    (net (code "8") (name "Net-(DA1-UOUT)") (class "Default")
      (node (ref "C26") (pin "2") (pinfunction "2_2") (pintype "passive"))
      (node (ref "DA1") (pin "1") (pinfunction "UOUT_1") (pintype "passive"))
      (node (ref "R2") (pin "1") (pinfunction "1_1") (pintype "passive"))
    )
    (net (code "9") (name "Net-(DA2-IN+)") (class "Default")
      (node (ref "DA2") (pin "3") (pinfunction "IN+_3") (pintype "passive"))
      (node (ref "R3") (pin "1") (pinfunction "1_1") (pintype "passive"))
      (node (ref "VT1") (pin "3") (pinfunction "D_3") (pintype "passive"))
    )
    (net (code "10") (name "Net-(DA2-IN-)") (class "Default")
      (node (ref "C27") (pin "1") (pinfunction "1_1") (pintype "passive"))
      (node (ref "DA2") (pin "4") (pinfunction "IN-_4") (pintype "passive"))
      (node (ref "R4") (pin "1") (pinfunction "1_1") (pintype "passive"))
    )
    (net (code "11") (name "Net-(DA2-UOUT)") (class "Default")
      (node (ref "C27") (pin "2") (pinfunction "2_2") (pintype "passive"))
      (node (ref "DA2") (pin "1") (pinfunction "UOUT_1") (pintype "passive"))
      (node (ref "R7") (pin "1") (pinfunction "1_1") (pintype "passive"))
    )
    (net (code "12") (name "Net-(DA4-IN+)") (class "Default")
      (node (ref "DA4") (pin "2") (pinfunction "IN+_2") (pintype "passive"))
      (node (ref "VT2") (pin "3") (pinfunction "S_3") (pintype "passive"))
      (node (ref "XS4") (pin "2") (pinfunction "Pin2_2") (pintype "passive"))
    )
    (net (code "13") (name "Net-(DA4-RG-Pad1)") (class "Default")
      (node (ref "DA4") (pin "1") (pinfunction "RG_1") (pintype "passive"))
      (node (ref "R12") (pin "2") (pinfunction "2_2") (pintype "passive"))
    )
    (net (code "14") (name "Net-(DA4-RG-Pad8)") (class "Default")
      (node (ref "DA4") (pin "8") (pinfunction "RG_8") (pintype "passive"))
      (node (ref "R12") (pin "1") (pinfunction "1_1") (pintype "passive"))
    )
    (net (code "15") (name "Net-(DA4-UOUT)") (class "Default")
      (node (ref "DA4") (pin "6") (pinfunction "UOUT_6") (pintype "passive"))
      (node (ref "DA5") (pin "2") (pinfunction "IN+_2") (pintype "passive"))
    )
    (net (code "16") (name "Net-(DA5-IN-)") (class "Default")
      (node (ref "DA5") (pin "3") (pinfunction "IN-_3") (pintype "passive"))
      (node (ref "R15") (pin "2") (pinfunction "2_2") (pintype "passive"))
      (node (ref "R17") (pin "2") (pinfunction "2_2") (pintype "passive"))
    )
    (net (code "17") (name "Net-(DA5-RG-Pad1)") (class "Default")
      (node (ref "DA5") (pin "1") (pinfunction "RG_1") (pintype "passive"))
      (node (ref "R13") (pin "2") (pinfunction "2_2") (pintype "passive"))
    )
    (net (code "18") (name "Net-(DA5-RG-Pad8)") (class "Default")
      (node (ref "DA5") (pin "8") (pinfunction "RG_8") (pintype "passive"))
      (node (ref "R13") (pin "1") (pinfunction "1_1") (pintype "passive"))
    )
    (net (code "19") (name "Net-(DA6-IN+)") (class "Default")
      (node (ref "DA6") (pin "2") (pinfunction "IN+_2") (pintype "passive"))
      (node (ref "R10") (pin "2") (pinfunction "2_2") (pintype "passive"))
      (node (ref "R11") (pin "1") (pinfunction "1_1") (pintype "passive"))
    )
    (net (code "20") (name "Net-(DA6-OUT)") (class "Default")
      (node (ref "DA6") (pin "7") (pinfunction "OUT_7") (pintype "passive"))
      (node (ref "DD1") (pin "4") (pintype "passive"))
    )
    (net (code "21") (name "Net-(DA7-IN-)") (class "Default")
      (node (ref "DA7") (pin "3") (pinfunction "IN-_3") (pintype "passive"))
      (node (ref "R16") (pin "2") (pinfunction "2_2") (pintype "passive"))
      (node (ref "R18") (pin "2") (pinfunction "2_2") (pintype "passive"))
    )
    (net (code "22") (name "Net-(DA7-OUT)") (class "Default")
      (node (ref "DA7") (pin "7") (pinfunction "OUT_7") (pintype "passive"))
      (node (ref "DD1") (pin "5") (pintype "passive"))
    )
    (net (code "23") (name "Net-(DA33-AIN1)") (class "Default")
      (node (ref "DA33") (pin "4") (pinfunction "AIN1_4") (pintype "passive"))
      (node (ref "DA5") (pin "6") (pinfunction "VOUT_6") (pintype "passive"))
      (node (ref "DA6") (pin "3") (pinfunction "IN-_3") (pintype "passive"))
      (node (ref "DA7") (pin "2") (pinfunction "IN+_2") (pintype "passive"))
    )
    (net (code "24") (name "Net-(DA33-DB0)") (class "Default")
      (node (ref "DA33") (pin "6") (pinfunction "DB0_6") (pintype "passive"))
      (node (ref "XS1") (pin "1") (pinfunction "Pin1_1") (pintype "passive"))
    )
    (net (code "25") (name "Net-(DA33-DB1)") (class "Default")
      (node (ref "DA33") (pin "7") (pinfunction "DB1_7") (pintype "passive"))
      (node (ref "XS1") (pin "2") (pinfunction "Pin2_2") (pintype "passive"))
    )
    (net (code "26") (name "Net-(DA33-DB2)") (class "Default")
      (node (ref "DA33") (pin "8") (pinfunction "DB2_8") (pintype "passive"))
      (node (ref "XS1") (pin "3") (pinfunction "Pin3_3") (pintype "passive"))
    )
    (net (code "27") (name "Net-(DA33-DB3)") (class "Default")
      (node (ref "DA33") (pin "9") (pinfunction "DB3_9") (pintype "passive"))
      (node (ref "XS1") (pin "4") (pinfunction "Pin4_4") (pintype "passive"))
    )
    (net (code "28") (name "Net-(DA33-DB4)") (class "Default")
      (node (ref "DA33") (pin "17") (pinfunction "DB4_17") (pintype "passive"))
      (node (ref "XS1") (pin "5") (pinfunction "Pin5_5") (pintype "passive"))
    )
    (net (code "29") (name "Net-(DA33-DB5)") (class "Default")
      (node (ref "DA33") (pin "18") (pinfunction "DB5_18") (pintype "passive"))
      (node (ref "XS1") (pin "6") (pinfunction "Pin6_6") (pintype "passive"))
    )
    (net (code "30") (name "Net-(DA33-DB6)") (class "Default")
      (node (ref "DA33") (pin "19") (pinfunction "DB6_19") (pintype "passive"))
      (node (ref "XS1") (pin "7") (pinfunction "Pin7_7") (pintype "passive"))
    )
    (net (code "31") (name "Net-(DA33-DB7)") (class "Default")
      (node (ref "DA33") (pin "20") (pinfunction "DB7_20") (pintype "passive"))
      (node (ref "XS1") (pin "8") (pinfunction "Pin8_8") (pintype "passive"))
    )
    (net (code "32") (name "Net-(DA33-UREF(+))") (class "Default")
      (node (ref "DA33") (pin "14") (pinfunction "UREF(+)_14") (pintype "passive"))
      (node (ref "DA4") (pin "3") (pinfunction "IN-_3") (pintype "passive"))
      (node (ref "R14") (pin "1") (pinfunction "1_1") (pintype "passive"))
      (node (ref "XS4") (pin "3") (pinfunction "3_3") (pintype "passive"))
    )
    (net (code "33") (name "Net-(DD1-Pad2)") (class "Default")
      (node (ref "DD1") (pin "2") (pintype "passive"))
      (node (ref "DD2") (pin "6") (pintype "passive"))
      (node (ref "R21") (pin "1") (pinfunction "1_1") (pintype "passive"))
      (node (ref "SB3") (pin "2") (pintype "passive"))
    )
    (net (code "34") (name "Net-(DD1-Pad13)") (class "Default")
      (node (ref "DD1") (pin "13") (pintype "passive"))
      (node (ref "DD4") (pin "2") (pintype "passive"))
      (node (ref "DD4") (pin "5") (pintype "passive"))
      (node (ref "R22") (pin "1") (pinfunction "1_1") (pintype "passive"))
      (node (ref "SB4") (pin "2") (pintype "passive"))
    )
    (net (code "35") (name "Net-(DD2-Pad10)") (class "Default")
      (node (ref "DD2") (pin "10") (pintype "passive"))
      (node (ref "DD6") (pin "11") (pintype "passive"))
    )
    (net (code "36") (name "Net-(DD2-Pad13)") (class "Default")
      (node (ref "DD2") (pin "13") (pintype "passive"))
      (node (ref "DD6") (pin "13") (pintype "passive"))
    )
    (net (code "37") (name "Net-(DD2-Pad14)") (class "Default")
      (node (ref "DD2") (pin "14") (pintype "passive"))
      (node (ref "R20") (pin "1") (pinfunction "1_1") (pintype "passive"))
      (node (ref "SB2") (pin "2") (pintype "passive"))
    )
    (net (code "38") (name "Net-(DD3-S0)") (class "Default")
      (node (ref "DD1") (pin "11") (pintype "passive"))
      (node (ref "DD2") (pin "4") (pintype "passive"))
      (node (ref "DD3") (pin "11") (pinfunction "S0_11") (pintype "passive"))
      (node (ref "DD5") (pin "11") (pinfunction "S0_11") (pintype "passive"))
      (node (ref "DD7") (pin "11") (pinfunction "S0_11") (pintype "passive"))
    )
    (net (code "39") (name "Net-(DD3-S1)") (class "Default")
      (node (ref "DD3") (pin "10") (pinfunction "S1_10") (pintype "passive"))
      (node (ref "DD4") (pin "3") (pintype "passive"))
      (node (ref "DD5") (pin "10") (pinfunction "S1_10") (pintype "passive"))
      (node (ref "DD6") (pin "12") (pintype "passive"))
      (node (ref "DD7") (pin "10") (pinfunction "S1_10") (pintype "passive"))
    )
    (net (code "40") (name "Net-(DD3-S2)") (class "Default")
      (node (ref "DD2") (pin "12") (pintype "passive"))
      (node (ref "DD3") (pin "9") (pinfunction "S2_9") (pintype "passive"))
      (node (ref "DD4") (pin "6") (pintype "passive"))
      (node (ref "DD5") (pin "9") (pinfunction "S2_9") (pintype "passive"))
      (node (ref "DD7") (pin "9") (pinfunction "S2_9") (pintype "passive"))
    )
    (net (code "41") (name "Net-(DD3-Y0)") (class "Default")
      (node (ref "DD1") (pin "10") (pintype "passive"))
      (node (ref "DD2") (pin "9") (pintype "passive"))
      (node (ref "DD3") (pin "13") (pinfunction "Y0_13") (pintype "passive"))
    )
    (net (code "42") (name "Net-(DD3-Y1)") (class "Default")
      (node (ref "DD1") (pin "8") (pintype "passive"))
      (node (ref "DD3") (pin "14") (pinfunction "Y1_14") (pintype "passive"))
    )
    (net (code "43") (name "Net-(DD3-Y4)") (class "Default")
      (node (ref "DD1") (pin "1") (pintype "passive"))
      (node (ref "DD3") (pin "1") (pinfunction "Y4_1") (pintype "passive"))
      (node (ref "R19") (pin "1") (pinfunction "1_1") (pintype "passive"))
      (node (ref "SB1") (pin "2") (pintype "passive"))
    )
    (net (code "44") (name "Net-(DD3-Z)") (class "Default")
      (node (ref "DD3") (pin "3") (pinfunction "Z_3") (pintype "passive"))
      (node (ref "DD4") (pin "4") (pintype "passive"))
    )
    (net (code "45") (name "Net-(DD5-Y0)") (class "Default")
      (node (ref "DD1") (pin "6") (pintype "passive"))
      (node (ref "DD1") (pin "9") (pintype "passive"))
      (node (ref "DD5") (pin "13") (pinfunction "Y0_13") (pintype "passive"))
    )
    (net (code "46") (name "Net-(DD5-Y2)") (class "Default")
      (node (ref "DD2") (pin "1") (pintype "passive"))
      (node (ref "DD5") (pin "15") (pinfunction "Y2_15") (pintype "passive"))
      (node (ref "DD7") (pin "14") (pinfunction "Y1_14") (pintype "passive"))
    )
    (net (code "47") (name "Net-(DD5-Z)") (class "Default")
      (node (ref "DD4") (pin "1") (pintype "passive"))
      (node (ref "DD5") (pin "3") (pinfunction "Z_3") (pintype "passive"))
    )
    (net (code "48") (name "Net-(DD7-Y0)") (class "Default")
      (node (ref "DD1") (pin "3") (pintype "passive"))
      (node (ref "DD7") (pin "13") (pinfunction "Y0_13") (pintype "passive"))
    )
    (net (code "49") (name "Net-(DD7-Z)") (class "Default")
      (node (ref "DD1") (pin "12") (pintype "passive"))
      (node (ref "DD7") (pin "3") (pinfunction "Z_3") (pintype "passive"))
    )
    (net (code "50") (name "Net-(VT1-G)") (class "Default")
      (node (ref "R2") (pin "2") (pinfunction "2_2") (pintype "passive"))
      (node (ref "VT1") (pin "1") (pinfunction "G_1") (pintype "passive"))
    )
    (net (code "51") (name "Net-(VT1-S)") (class "Default")
      (node (ref "R8") (pin "2") (pinfunction "2_2") (pintype "passive"))
      (node (ref "R9") (pin "2") (pinfunction "2_2") (pintype "passive"))
      (node (ref "VT1") (pin "2") (pinfunction "S_2") (pintype "passive"))
    )
    (net (code "52") (name "Net-(VT2-D)") (class "Default")
      (node (ref "R4") (pin "2") (pinfunction "2_2") (pintype "passive"))
      (node (ref "R5") (pin "1") (pinfunction "1_1") (pintype "passive"))
      (node (ref "VT2") (pin "2") (pinfunction "D_2") (pintype "passive"))
    )
    (net (code "53") (name "Net-(XS5-Pin1)") (class "Default")
      (node (ref "DD6") (pin "10") (pintype "passive"))
      (node (ref "XS5") (pin "1") (pinfunction "Pin1_1") (pintype "passive"))
    )
    (net (code "54") (name "unconnected-(DA6-LATCH-Pad5)") (class "Default")
      (node (ref "DA6") (pin "5") (pinfunction "LATCH_5") (pintype "passive"))
    )
    (net (code "55") (name "unconnected-(DA6-~{OUT}-Pad8)") (class "Default")
      (node (ref "DA6") (pin "8") (pinfunction "~{OUT}_8") (pintype "passive"))
    )
    (net (code "56") (name "unconnected-(DA7-LATCH-Pad5)") (class "Default")
      (node (ref "DA7") (pin "5") (pinfunction "LATCH_5") (pintype "passive"))
    )
    (net (code "57") (name "unconnected-(DA7-~{OUT}-Pad8)") (class "Default")
      (node (ref "DA7") (pin "8") (pinfunction "~{OUT}_8") (pintype "passive"))
    )
    (net (code "58") (name "unconnected-(DA33-AIN2-Pad3)") (class "Default")
      (node (ref "DA33") (pin "3") (pinfunction "AIN2_3") (pintype "passive"))
    )
    (net (code "59") (name "unconnected-(DA33-AIN3-Pad2)") (class "Default")
      (node (ref "DA33") (pin "2") (pinfunction "AIN3_2") (pintype "passive"))
    )
    (net (code "60") (name "unconnected-(DA33-AIN4-Pad1)") (class "Default")
      (node (ref "DA33") (pin "1") (pinfunction "AIN4_1") (pintype "passive"))
    )
    (net (code "61") (name "unconnected-(DA33-NC-Pad5)") (class "Default")
      (node (ref "DA33") (pin "5") (pinfunction "NC_5") (pintype "passive"))
    )
    (net (code "62") (name "unconnected-(DA33-NC-Pad23)") (class "Default")
      (node (ref "DA33") (pin "23") (pinfunction "NC_23") (pintype "passive"))
    )
    (net (code "63") (name "unconnected-(R7-Pad2)") (class "Default")
      (node (ref "R7") (pin "2") (pinfunction "2_2") (pintype "passive"))
    )
    (net (code "64") (name "unconnected-(VT2-G-Pad1)") (class "Default")
      (node (ref "VT2") (pin "1") (pinfunction "G_1") (pintype "passive"))
    )
  )
)
